# schematic.net
KiCad netlist of a schematic drawn in EAGLE
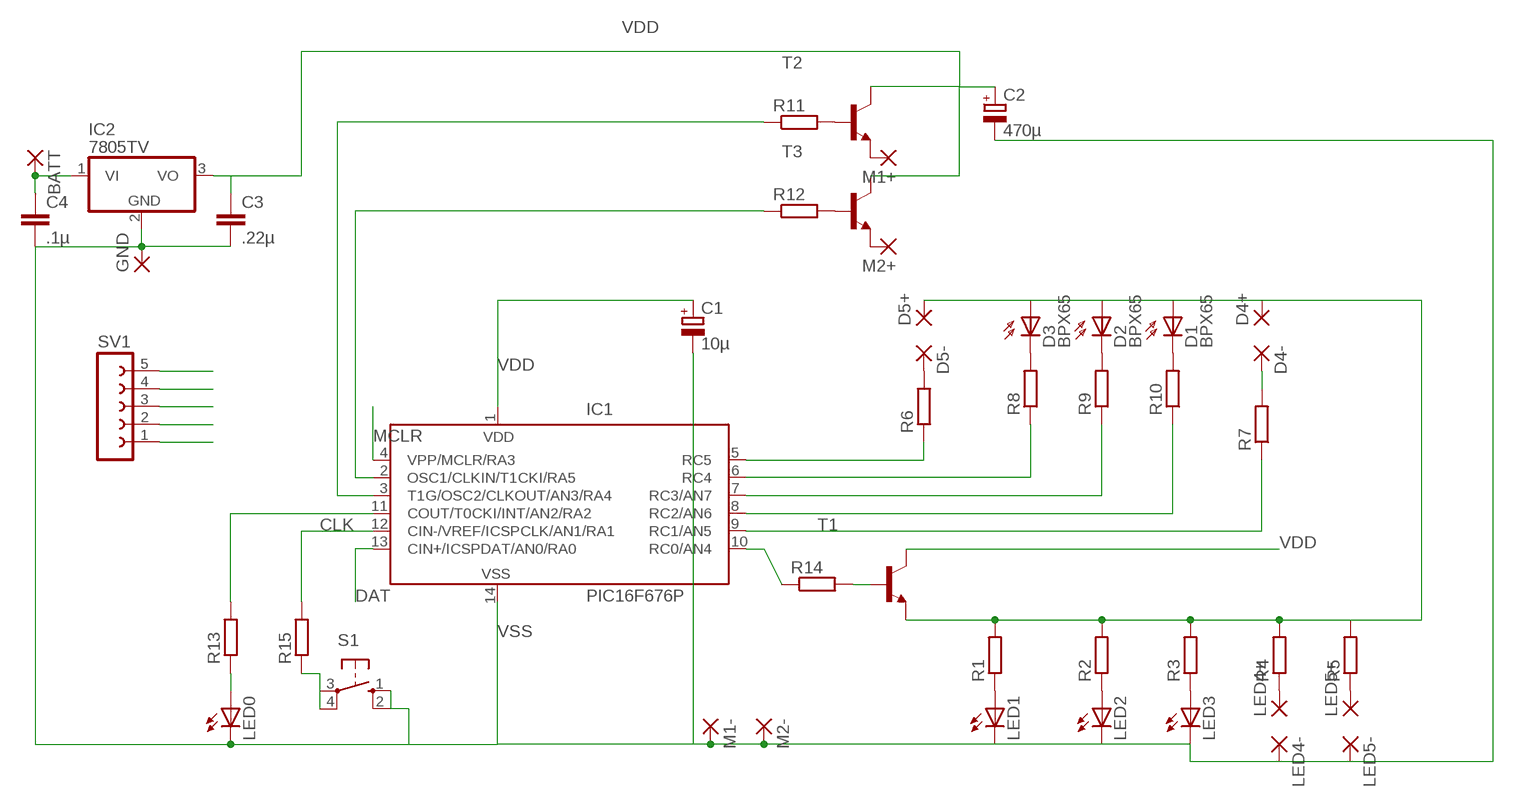
[diagram p0: schematic, sheet 1]

(export (version "E")
  (design (tool "Eeschema 10.0.6"))
  (components
    (comp (ref "BATT")
      (value "2,15/1,0")
      (footprint "eagle-import:2,15_1,0")
      (libsource (lib "eagle-import") (part "2,15/1,0"))
    )
    (comp (ref "C1")
      (value "10µ")
      (footprint "eagle-import:E2,5-5")
      (libsource (lib "eagle-import") (part "CPOL-EUE2.5-5"))
    )
    (comp (ref "C2")
      (value "470µ")
      (footprint "eagle-import:E2,5-7")
      (libsource (lib "eagle-import") (part "CPOL-EUE2.5-7"))
    )
    (comp (ref "C3")
      (value ".22µ")
      (footprint "eagle-import:C050-025X075")
      (libsource (lib "eagle-import") (part "C-EU050-025X075"))
    )
    (comp (ref "C4")
      (value ".1µ")
      (footprint "eagle-import:C050-025X075")
      (libsource (lib "eagle-import") (part "C-EU050-025X075"))
    )
    (comp (ref "D1")
      (value "BPX65")
      (footprint "eagle-import:BPX65")
      (fields (field (name "MPN") "BPX65."))
      (libsource (lib "eagle-import") (part "BPX65"))
    )
    (comp (ref "D2")
      (value "BPX65")
      (footprint "eagle-import:BPX65")
      (fields (field (name "MPN") "BPX65."))
      (libsource (lib "eagle-import") (part "BPX65"))
    )
    (comp (ref "D3")
      (value "BPX65")
      (footprint "eagle-import:BPX65")
      (fields (field (name "MPN") "BPX65."))
      (libsource (lib "eagle-import") (part "BPX65"))
    )
    (comp (ref "D4+")
      (value "2,15/1,0")
      (footprint "eagle-import:2,15_1,0")
      (libsource (lib "eagle-import") (part "2,15/1,0"))
    )
    (comp (ref "D4-")
      (value "2,15/1,0")
      (footprint "eagle-import:2,15_1,0")
      (libsource (lib "eagle-import") (part "2,15/1,0"))
    )
    (comp (ref "D5+")
      (value "2,15/1,0")
      (footprint "eagle-import:2,15_1,0")
      (libsource (lib "eagle-import") (part "2,15/1,0"))
    )
    (comp (ref "D5-")
      (value "2,15/1,0")
      (footprint "eagle-import:2,15_1,0")
      (libsource (lib "eagle-import") (part "2,15/1,0"))
    )
    (comp (ref "GND")
      (value "2,15/1,0")
      (footprint "eagle-import:2,15_1,0")
      (libsource (lib "eagle-import") (part "2,15/1,0"))
    )
    (comp (ref "IC1")
      (value "PIC16F676P")
      (footprint "eagle-import:DIL14")
      (fields (field (name "MF") "MICROCHIP") (field (name "MPN") "PIC16F676-I/P"))
      (libsource (lib "eagle-import") (part "PIC16F676P"))
    )
    (comp (ref "IC2")
      (value "7805TV")
      (footprint "eagle-import:TO220V")
      (libsource (lib "eagle-import") (part "78TV05"))
    )
    (comp (ref "LED0")
      (value "LED3MM")
      (footprint "eagle-import:LED3MM")
      (libsource (lib "eagle-import") (part "LED3MM"))
    )
    (comp (ref "LED1")
      (value "LED3MM")
      (footprint "eagle-import:LED3MM")
      (libsource (lib "eagle-import") (part "LED3MM"))
    )
    (comp (ref "LED2")
      (value "LED3MM")
      (footprint "eagle-import:LED3MM")
      (libsource (lib "eagle-import") (part "LED3MM"))
    )
    (comp (ref "LED3")
      (value "LED3MM")
      (footprint "eagle-import:LED3MM")
      (libsource (lib "eagle-import") (part "LED3MM"))
    )
    (comp (ref "LED4+")
      (value "2,15/1,0")
      (footprint "eagle-import:2,15_1,0")
      (libsource (lib "eagle-import") (part "2,15/1,0"))
    )
    (comp (ref "LED4-")
      (value "2,15/1,0")
      (footprint "eagle-import:2,15_1,0")
      (libsource (lib "eagle-import") (part "2,15/1,0"))
    )
    (comp (ref "LED5+")
      (value "2,15/1,0")
      (footprint "eagle-import:2,15_1,0")
      (libsource (lib "eagle-import") (part "2,15/1,0"))
    )
    (comp (ref "LED5-")
      (value "2,15/1,0")
      (footprint "eagle-import:2,15_1,0")
      (libsource (lib "eagle-import") (part "2,15/1,0"))
    )
    (comp (ref "M1+")
      (value "2,15/1,0")
      (footprint "eagle-import:2,15_1,0")
      (libsource (lib "eagle-import") (part "2,15/1,0"))
    )
    (comp (ref "M1-")
      (value "2,15/1,0")
      (footprint "eagle-import:2,15_1,0")
      (libsource (lib "eagle-import") (part "2,15/1,0"))
    )
    (comp (ref "M2+")
      (value "2,15/1,0")
      (footprint "eagle-import:2,15_1,0")
      (libsource (lib "eagle-import") (part "2,15/1,0"))
    )
    (comp (ref "M2-")
      (value "2,15/1,0")
      (footprint "eagle-import:2,15_1,0")
      (libsource (lib "eagle-import") (part "2,15/1,0"))
    )
    (comp (ref "R1")
      (value "R-EU_0204/7")
      (footprint "eagle-import:0204_7")
      (libsource (lib "eagle-import") (part "R-EU_0204/7"))
    )
    (comp (ref "R2")
      (value "R-EU_0204/7")
      (footprint "eagle-import:0204_7")
      (libsource (lib "eagle-import") (part "R-EU_0204/7"))
    )
    (comp (ref "R3")
      (value "R-EU_0204/7")
      (footprint "eagle-import:0204_7")
      (libsource (lib "eagle-import") (part "R-EU_0204/7"))
    )
    (comp (ref "R4")
      (value "R-EU_0204/7")
      (footprint "eagle-import:0204_7")
      (libsource (lib "eagle-import") (part "R-EU_0204/7"))
    )
    (comp (ref "R5")
      (value "R-EU_0204/7")
      (footprint "eagle-import:0204_7")
      (libsource (lib "eagle-import") (part "R-EU_0204/7"))
    )
    (comp (ref "R6")
      (value "R-EU_0204/7")
      (footprint "eagle-import:0204_7")
      (libsource (lib "eagle-import") (part "R-EU_0204/7"))
    )
    (comp (ref "R7")
      (value "R-EU_0204/7")
      (footprint "eagle-import:0204_7")
      (libsource (lib "eagle-import") (part "R-EU_0204/7"))
    )
    (comp (ref "R8")
      (value "R-EU_0204/7")
      (footprint "eagle-import:0204_7")
      (libsource (lib "eagle-import") (part "R-EU_0204/7"))
    )
    (comp (ref "R9")
      (value "R-EU_0204/7")
      (footprint "eagle-import:0204_7")
      (libsource (lib "eagle-import") (part "R-EU_0204/7"))
    )
    (comp (ref "R10")
      (value "R-EU_0204/7")
      (footprint "eagle-import:0204_7")
      (libsource (lib "eagle-import") (part "R-EU_0204/7"))
    )
    (comp (ref "R11")
      (value "R-EU_0204/7")
      (footprint "eagle-import:0204_7")
      (libsource (lib "eagle-import") (part "R-EU_0204/7"))
    )
    (comp (ref "R12")
      (value "R-EU_0204/7")
      (footprint "eagle-import:0204_7")
      (libsource (lib "eagle-import") (part "R-EU_0204/7"))
    )
    (comp (ref "R13")
      (value "R-EU_0204/7")
      (footprint "eagle-import:0204_7")
      (libsource (lib "eagle-import") (part "R-EU_0204/7"))
    )
    (comp (ref "R14")
      (value "R-EU_0204/7")
      (footprint "eagle-import:0204_7")
      (libsource (lib "eagle-import") (part "R-EU_0204/7"))
    )
    (comp (ref "R15")
      (value "R-EU_0204/7")
      (footprint "eagle-import:0204_7")
      (libsource (lib "eagle-import") (part "R-EU_0204/7"))
    )
    (comp (ref "S1")
      (value "10-XX")
      (footprint "eagle-import:B3F-10XX")
      (fields (field (name "MPN") "B3F-1000"))
      (libsource (lib "eagle-import") (part "10-XX"))
    )
    (comp (ref "SV1")
      (value "FE05-1")
      (footprint "eagle-import:FE05-1")
      (libsource (lib "eagle-import") (part "FE05-1"))
    )
    (comp (ref "T1")
      (value "-NPN-TO92")
      (footprint "eagle-import:TO92")
      (libsource (lib "eagle-import") (part "-NPN-TO92"))
    )
    (comp (ref "T2")
      (value "-NPN-TO92")
      (footprint "eagle-import:TO92")
      (libsource (lib "eagle-import") (part "-NPN-TO92"))
    )
    (comp (ref "T3")
      (value "-NPN-TO92")
      (footprint "eagle-import:TO92")
      (libsource (lib "eagle-import") (part "-NPN-TO92"))
    )
  )
  (nets
    (net (code "1") (name "/CLK") (class "Default")
      (node (ref "IC1") (pin "12") (pinfunction "CIN-/VREF/ICSPCLK/AN1/RA1_12") (pintype "bidirectional"))
      (node (ref "R15") (pin "2") (pinfunction "2_2") (pintype "passive"))
      (node (ref "SV1") (pin "5") (pinfunction "5_5") (pintype "passive"))
    )
    (net (code "2") (name "/DAT") (class "Default")
      (node (ref "IC1") (pin "13") (pinfunction "CIN+/ICSPDAT/AN0/RA0_13") (pintype "bidirectional"))
      (node (ref "SV1") (pin "4") (pinfunction "4_4") (pintype "passive"))
    )
    (net (code "3") (name "/MCLR") (class "Default")
      (node (ref "IC1") (pin "4") (pinfunction "VPP/MCLR/RA3_4") (pintype "input"))
      (node (ref "SV1") (pin "1") (pinfunction "1_1") (pintype "passive"))
    )
    (net (code "4") (name "/VDD") (class "Default")
      (node (ref "C1") (pin "+") (pinfunction "+_+") (pintype "passive"))
      (node (ref "C2") (pin "+") (pinfunction "+_+") (pintype "passive"))
      (node (ref "C3") (pin "1") (pinfunction "1_1") (pintype "passive"))
      (node (ref "IC1") (pin "1") (pinfunction "VDD_1") (pintype "power_in"))
      (node (ref "IC2") (pin "3") (pinfunction "VO_3") (pintype "passive"))
      (node (ref "SV1") (pin "2") (pinfunction "2_2") (pintype "passive"))
      (node (ref "T1") (pin "3") (pinfunction "C_3") (pintype "passive"))
      (node (ref "T2") (pin "3") (pinfunction "C_3") (pintype "passive"))
      (node (ref "T3") (pin "3") (pinfunction "C_3") (pintype "passive"))
    )
    (net (code "5") (name "/VSS") (class "Default")
      (node (ref "C1") (pin "-") (pinfunction "-_-") (pintype "passive"))
      (node (ref "C2") (pin "-") (pinfunction "-_-") (pintype "passive"))
      (node (ref "C3") (pin "2") (pinfunction "2_2") (pintype "passive"))
      (node (ref "C4") (pin "2") (pinfunction "2_2") (pintype "passive"))
      (node (ref "GND") (pin "1") (pinfunction "P_1") (pintype "passive"))
      (node (ref "IC1") (pin "14") (pinfunction "VSS_14") (pintype "power_in"))
      (node (ref "IC2") (pin "2") (pinfunction "GND_2") (pintype "passive"))
      (node (ref "LED0") (pin "K") (pinfunction "C_K") (pintype "passive"))
      (node (ref "LED1") (pin "K") (pinfunction "C_K") (pintype "passive"))
      (node (ref "LED2") (pin "K") (pinfunction "C_K") (pintype "passive"))
      (node (ref "LED3") (pin "K") (pinfunction "C_K") (pintype "passive"))
      (node (ref "LED4-") (pin "1") (pinfunction "P_1") (pintype "passive"))
      (node (ref "LED5-") (pin "1") (pinfunction "P_1") (pintype "passive"))
      (node (ref "M1-") (pin "1") (pinfunction "P_1") (pintype "passive"))
      (node (ref "M2-") (pin "1") (pinfunction "P_1") (pintype "passive"))
      (node (ref "S1") (pin "1") (pinfunction "S_1") (pintype "passive"))
      (node (ref "S1") (pin "2") (pinfunction "S1_2") (pintype "passive"))
      (node (ref "SV1") (pin "3") (pinfunction "3_3") (pintype "passive"))
    )
    (net (code "6") (name "Net-(BATT-P)") (class "Default")
      (node (ref "BATT") (pin "1") (pinfunction "P_1") (pintype "passive"))
      (node (ref "C4") (pin "1") (pinfunction "1_1") (pintype "passive"))
      (node (ref "IC2") (pin "1") (pinfunction "VI_1") (pintype "input"))
    )
    (net (code "7") (name "Net-(D1-C)") (class "Default")
      (node (ref "D1") (pin "K") (pinfunction "C_K") (pintype "passive"))
      (node (ref "R10") (pin "2") (pinfunction "2_2") (pintype "passive"))
    )
    (net (code "8") (name "Net-(D2-C)") (class "Default")
      (node (ref "D2") (pin "K") (pinfunction "C_K") (pintype "passive"))
      (node (ref "R9") (pin "2") (pinfunction "2_2") (pintype "passive"))
    )
    (net (code "9") (name "Net-(D3-C)") (class "Default")
      (node (ref "D3") (pin "K") (pinfunction "C_K") (pintype "passive"))
      (node (ref "R8") (pin "2") (pinfunction "2_2") (pintype "passive"))
    )
    (net (code "10") (name "Net-(D4+-P)") (class "Default")
      (node (ref "D1") (pin "A") (pinfunction "A_A") (pintype "passive"))
      (node (ref "D2") (pin "A") (pinfunction "A_A") (pintype "passive"))
      (node (ref "D3") (pin "A") (pinfunction "A_A") (pintype "passive"))
      (node (ref "D4+") (pin "1") (pinfunction "P_1") (pintype "passive"))
      (node (ref "D5+") (pin "1") (pinfunction "P_1") (pintype "passive"))
      (node (ref "R1") (pin "2") (pinfunction "2_2") (pintype "passive"))
      (node (ref "R2") (pin "2") (pinfunction "2_2") (pintype "passive"))
      (node (ref "R3") (pin "2") (pinfunction "2_2") (pintype "passive"))
      (node (ref "R4") (pin "2") (pinfunction "2_2") (pintype "passive"))
      (node (ref "R5") (pin "2") (pinfunction "2_2") (pintype "passive"))
      (node (ref "T1") (pin "1") (pinfunction "E_1") (pintype "passive"))
    )
    (net (code "11") (name "Net-(D4--P)") (class "Default")
      (node (ref "D4-") (pin "1") (pinfunction "P_1") (pintype "passive"))
      (node (ref "R7") (pin "2") (pinfunction "2_2") (pintype "passive"))
    )
    (net (code "12") (name "Net-(D5--P)") (class "Default")
      (node (ref "D5-") (pin "1") (pinfunction "P_1") (pintype "passive"))
      (node (ref "R6") (pin "2") (pinfunction "2_2") (pintype "passive"))
    )
    (net (code "13") (name "Net-(IC1-COUT{slash}T0CKI{slash}INT{slash}AN2{slash}RA2)") (class "Default")
      (node (ref "IC1") (pin "11") (pinfunction "COUT/T0CKI/INT/AN2/RA2_11") (pintype "bidirectional"))
      (node (ref "R13") (pin "2") (pinfunction "2_2") (pintype "passive"))
    )
    (net (code "14") (name "Net-(IC1-OSC1{slash}CLKIN{slash}T1CKI{slash}RA5)") (class "Default")
      (node (ref "IC1") (pin "2") (pinfunction "OSC1/CLKIN/T1CKI/RA5_2") (pintype "bidirectional"))
      (node (ref "R12") (pin "1") (pinfunction "1_1") (pintype "passive"))
    )
    (net (code "15") (name "Net-(IC1-RC0{slash}AN4)") (class "Default")
      (node (ref "IC1") (pin "10") (pinfunction "RC0/AN4_10") (pintype "bidirectional"))
      (node (ref "R14") (pin "1") (pinfunction "1_1") (pintype "passive"))
    )
    (net (code "16") (name "Net-(IC1-RC1{slash}AN5)") (class "Default")
      (node (ref "IC1") (pin "9") (pinfunction "RC1/AN5_9") (pintype "bidirectional"))
      (node (ref "R7") (pin "1") (pinfunction "1_1") (pintype "passive"))
    )
    (net (code "17") (name "Net-(IC1-RC2{slash}AN6)") (class "Default")
      (node (ref "IC1") (pin "8") (pinfunction "RC2/AN6_8") (pintype "bidirectional"))
      (node (ref "R10") (pin "1") (pinfunction "1_1") (pintype "passive"))
    )
    (net (code "18") (name "Net-(IC1-RC3{slash}AN7)") (class "Default")
      (node (ref "IC1") (pin "7") (pinfunction "RC3/AN7_7") (pintype "bidirectional"))
      (node (ref "R9") (pin "1") (pinfunction "1_1") (pintype "passive"))
    )
    (net (code "19") (name "Net-(IC1-RC4)") (class "Default")
      (node (ref "IC1") (pin "6") (pinfunction "RC4_6") (pintype "bidirectional"))
      (node (ref "R8") (pin "1") (pinfunction "1_1") (pintype "passive"))
    )
    (net (code "20") (name "Net-(IC1-RC5)") (class "Default")
      (node (ref "IC1") (pin "5") (pinfunction "RC5_5") (pintype "bidirectional"))
      (node (ref "R6") (pin "1") (pinfunction "1_1") (pintype "passive"))
    )
    (net (code "21") (name "Net-(IC1-T1G{slash}OSC2{slash}CLKOUT{slash}AN3{slash}RA4)") (class "Default")
      (node (ref "IC1") (pin "3") (pinfunction "T1G/OSC2/CLKOUT/AN3/RA4_3") (pintype "bidirectional"))
      (node (ref "R11") (pin "1") (pinfunction "1_1") (pintype "passive"))
    )
    (net (code "22") (name "Net-(LED0-PadA)") (class "Default")
      (node (ref "LED0") (pin "A") (pinfunction "A_A") (pintype "passive"))
      (node (ref "R13") (pin "1") (pinfunction "1_1") (pintype "passive"))
    )
    (net (code "23") (name "Net-(LED1-PadA)") (class "Default")
      (node (ref "LED1") (pin "A") (pinfunction "A_A") (pintype "passive"))
      (node (ref "R1") (pin "1") (pinfunction "1_1") (pintype "passive"))
    )
    (net (code "24") (name "Net-(LED2-PadA)") (class "Default")
      (node (ref "LED2") (pin "A") (pinfunction "A_A") (pintype "passive"))
      (node (ref "R2") (pin "1") (pinfunction "1_1") (pintype "passive"))
    )
    (net (code "25") (name "Net-(LED3-PadA)") (class "Default")
      (node (ref "LED3") (pin "A") (pinfunction "A_A") (pintype "passive"))
      (node (ref "R3") (pin "1") (pinfunction "1_1") (pintype "passive"))
    )
    (net (code "26") (name "Net-(LED4+-P)") (class "Default")
      (node (ref "LED4+") (pin "1") (pinfunction "P_1") (pintype "passive"))
      (node (ref "R4") (pin "1") (pinfunction "1_1") (pintype "passive"))
    )
    (net (code "27") (name "Net-(LED5+-P)") (class "Default")
      (node (ref "LED5+") (pin "1") (pinfunction "P_1") (pintype "passive"))
      (node (ref "R5") (pin "1") (pinfunction "1_1") (pintype "passive"))
    )
    (net (code "28") (name "Net-(M1+-P)") (class "Default")
      (node (ref "M1+") (pin "1") (pinfunction "P_1") (pintype "passive"))
      (node (ref "T2") (pin "1") (pinfunction "E_1") (pintype "passive"))
    )
    (net (code "29") (name "Net-(M2+-P)") (class "Default")
      (node (ref "M2+") (pin "1") (pinfunction "P_1") (pintype "passive"))
      (node (ref "T3") (pin "1") (pinfunction "E_1") (pintype "passive"))
    )
    (net (code "30") (name "Net-(S1-P)") (class "Default")
      (node (ref "R15") (pin "1") (pinfunction "1_1") (pintype "passive"))
      (node (ref "S1") (pin "3") (pinfunction "P_3") (pintype "passive"))
      (node (ref "S1") (pin "4") (pinfunction "P1_4") (pintype "passive"))
    )
    (net (code "31") (name "Net-(T1-B)") (class "Default")
      (node (ref "R14") (pin "2") (pinfunction "2_2") (pintype "passive"))
      (node (ref "T1") (pin "2") (pinfunction "B_2") (pintype "passive"))
    )
    (net (code "32") (name "Net-(T2-B)") (class "Default")
      (node (ref "R11") (pin "2") (pinfunction "2_2") (pintype "passive"))
      (node (ref "T2") (pin "2") (pinfunction "B_2") (pintype "passive"))
    )
    (net (code "33") (name "Net-(T3-B)") (class "Default")
      (node (ref "R12") (pin "2") (pinfunction "2_2") (pintype "passive"))
      (node (ref "T3") (pin "2") (pinfunction "B_2") (pintype "passive"))
    )
  )
)
